# MOTOR_DRIVER.net
KiCad netlist of a schematic drawn in Altium Designer
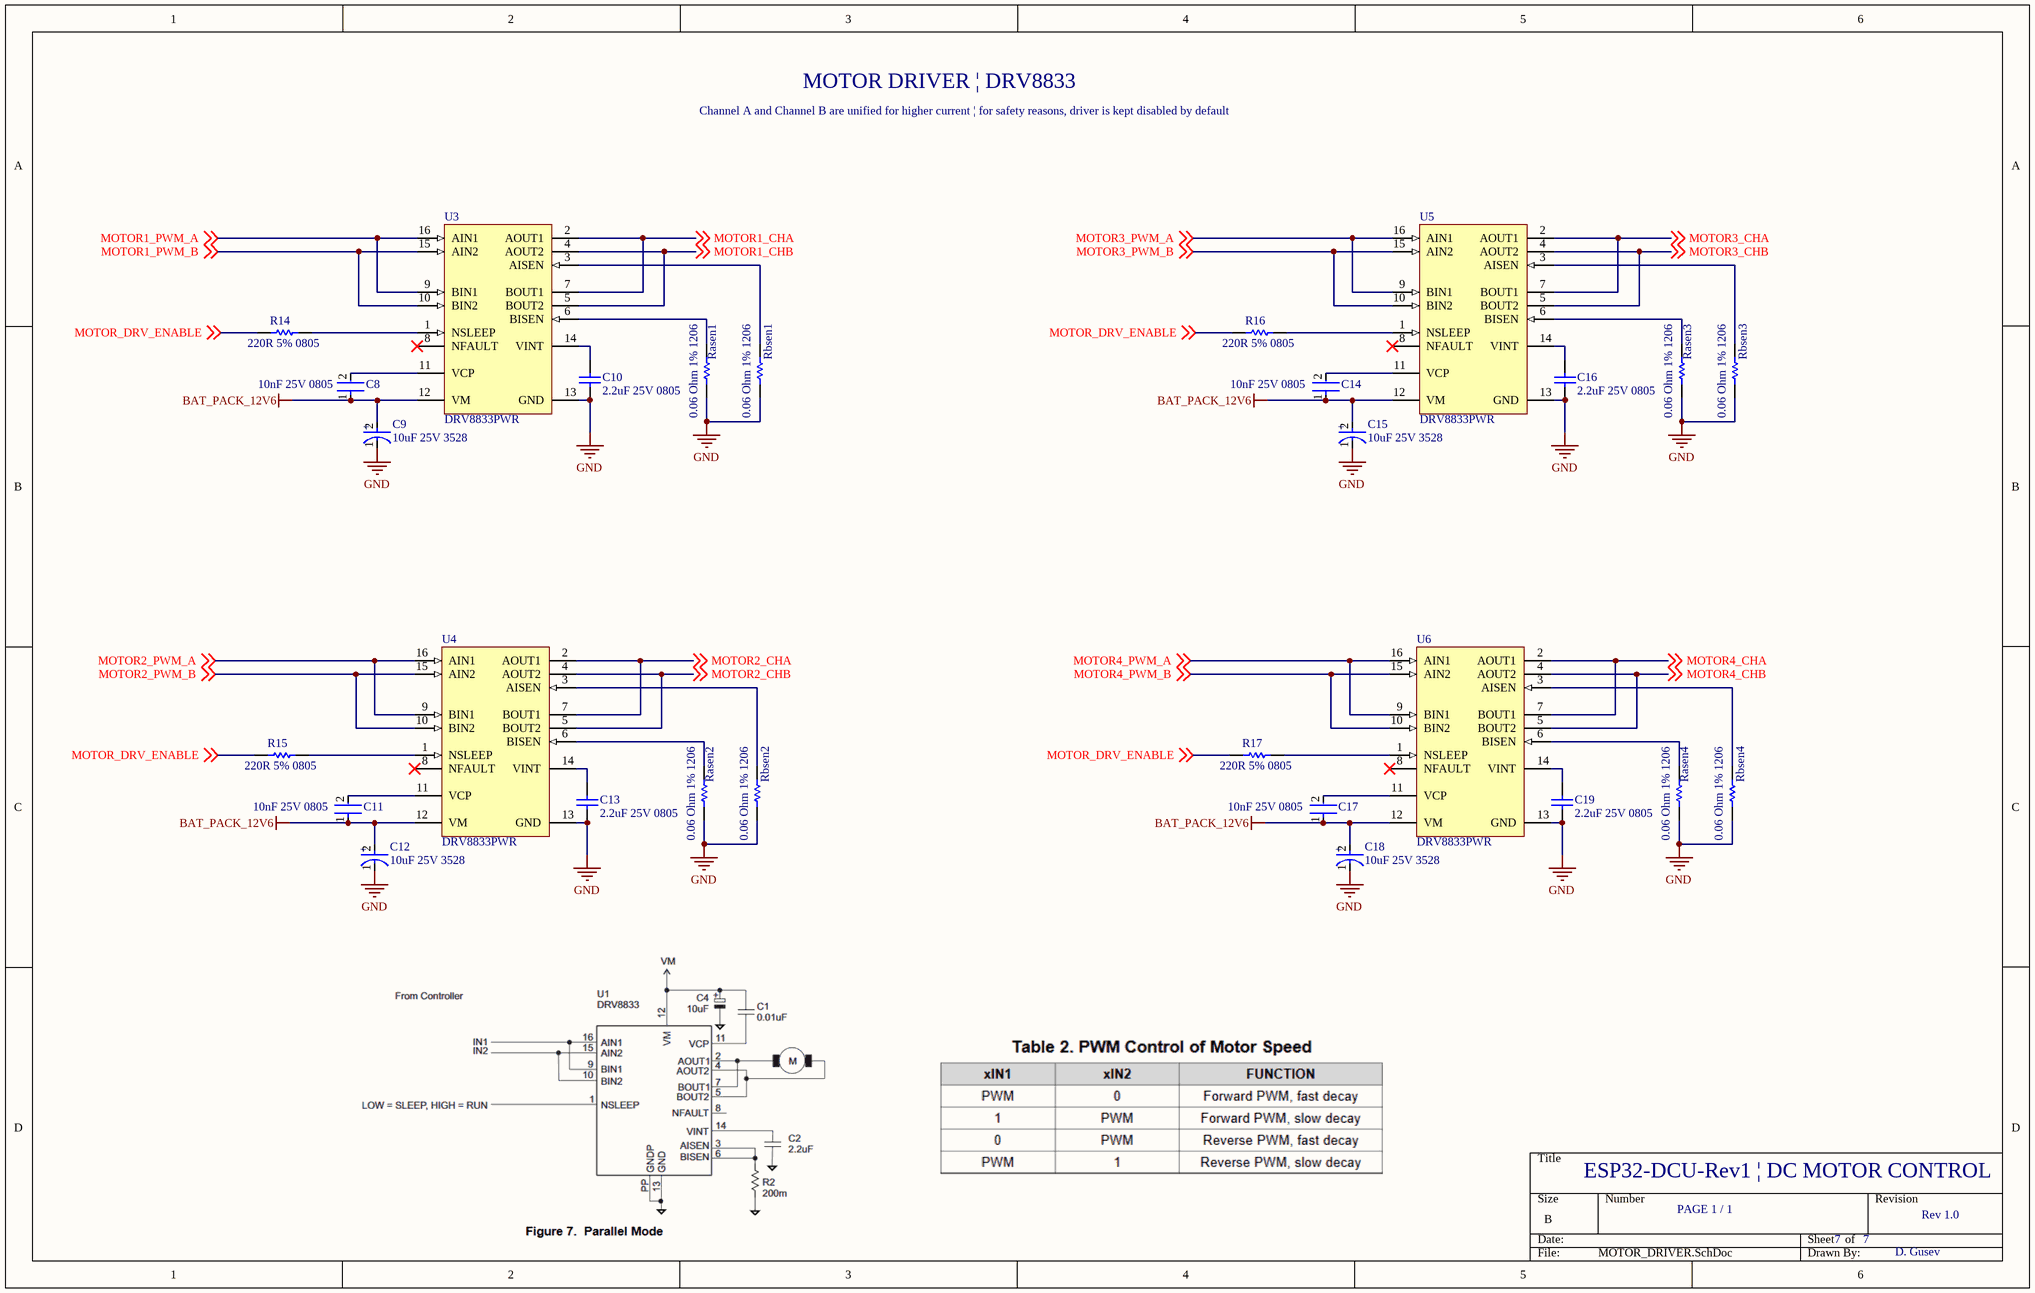
[diagram p0: MOTOR_DRIVER.SchDoc]

(export (version "E")
  (design (tool "Eeschema 10.0.6"))
  (components
    (comp (ref "C8")
      (value "10nF 25V 0805")
      (footprint "FP-C0805C-DN-MFG")
      (description "CAP CER 10000PF 25V 5% NP0 0805")
      (fields
        (field (name "OCTOPART") "https://octopart.com/c0805c103j3gactu-kemet-12563663")
        (field (name "TOLERANCE") "0.05")
      )
      (libsource (lib "Altium Content Vault") (part "b4654b650e69147ec39a6b967a45e02"))
    )
    (comp (ref "C9")
      (value "10uF 25V 3528")
      (footprint "FP-T491B106K025AT-MFG")
      (description "CAP TANT 10UF 10% 25V 1411")
      (fields (field (name "VOLTAGE") "25V") (field (name "TOLERANCE") "10%"))
      (libsource (lib "Altium Content Vault") (part "a00bbbee19879c290e62620ae7e47b1"))
    )
    (comp (ref "C10")
      (value "2.2uF 25V 0805")
      (footprint "CAPC2013X135X45ML10T25")
      (fields (field (name "PART NUMBER") "GRM21BF51E225ZA01L") (field (name "MANUFACTURER") "Murata"))
      (libsource (lib "Altium Content Vault") (part "CAP"))
    )
    (comp (ref "C11")
      (value "10nF 25V 0805")
      (footprint "FP-C0805C-DN-MFG")
      (description "CAP CER 10000PF 25V 5% NP0 0805")
      (fields
        (field (name "OCTOPART") "https://octopart.com/c0805c103j3gactu-kemet-12563663")
        (field (name "TOLERANCE") "0.05")
      )
      (libsource (lib "Altium Content Vault") (part "b4654b650e69147ec39a6b967a45e02"))
    )
    (comp (ref "C12")
      (value "10uF 25V 3528")
      (footprint "FP-T491B106K025AT-MFG")
      (description "CAP TANT 10UF 10% 25V 1411")
      (fields (field (name "VOLTAGE") "25V") (field (name "TOLERANCE") "10%"))
      (libsource (lib "Altium Content Vault") (part "a00bbbee19879c290e62620ae7e47b1"))
    )
    (comp (ref "C13")
      (value "2.2uF 25V 0805")
      (footprint "CAPC2013X135X45ML10T25")
      (fields (field (name "PART NUMBER") "GRM21BF51E225ZA01L") (field (name "MANUFACTURER") "Murata"))
      (libsource (lib "Altium Content Vault") (part "CAP"))
    )
    (comp (ref "C14")
      (value "10nF 25V 0805")
      (footprint "FP-C0805C-DN-MFG")
      (description "CAP CER 10000PF 25V 5% NP0 0805")
      (fields
        (field (name "OCTOPART") "https://octopart.com/c0805c103j3gactu-kemet-12563663")
        (field (name "TOLERANCE") "0.05")
      )
      (libsource (lib "Altium Content Vault") (part "b4654b650e69147ec39a6b967a45e02"))
    )
    (comp (ref "C15")
      (value "10uF 25V 3528")
      (footprint "FP-T491B106K025AT-MFG")
      (description "CAP TANT 10UF 10% 25V 1411")
      (fields (field (name "VOLTAGE") "25V") (field (name "TOLERANCE") "10%"))
      (libsource (lib "Altium Content Vault") (part "a00bbbee19879c290e62620ae7e47b1"))
    )
    (comp (ref "C16")
      (value "2.2uF 25V 0805")
      (footprint "CAPC2013X135X45ML10T25")
      (fields (field (name "PART NUMBER") "GRM21BF51E225ZA01L") (field (name "MANUFACTURER") "Murata"))
      (libsource (lib "Altium Content Vault") (part "CAP"))
    )
    (comp (ref "C17")
      (value "10nF 25V 0805")
      (footprint "FP-C0805C-DN-MFG")
      (description "CAP CER 10000PF 25V 5% NP0 0805")
      (fields
        (field (name "OCTOPART") "https://octopart.com/c0805c103j3gactu-kemet-12563663")
        (field (name "TOLERANCE") "0.05")
      )
      (libsource (lib "Altium Content Vault") (part "b4654b650e69147ec39a6b967a45e02"))
    )
    (comp (ref "C18")
      (value "10uF 25V 3528")
      (footprint "FP-T491B106K025AT-MFG")
      (description "CAP TANT 10UF 10% 25V 1411")
      (fields (field (name "VOLTAGE") "25V") (field (name "TOLERANCE") "10%"))
      (libsource (lib "Altium Content Vault") (part "a00bbbee19879c290e62620ae7e47b1"))
    )
    (comp (ref "C19")
      (value "2.2uF 25V 0805")
      (footprint "CAPC2013X135X45ML10T25")
      (fields (field (name "PART NUMBER") "GRM21BF51E225ZA01L") (field (name "MANUFACTURER") "Murata"))
      (libsource (lib "Altium Content Vault") (part "CAP"))
    )
    (comp (ref "R14")
      (value "220R 5% 0805")
      (footprint "RESC2013X60X40NL20T25")
      (fields (field (name "MANUFACTURER") "Panasonic") (field (name "PART NUMBER") "ERA6AEB221V"))
      (libsource (lib "Altium Content Vault") (part "RES"))
    )
    (comp (ref "R15")
      (value "220R 5% 0805")
      (footprint "RESC2013X60X40NL20T25")
      (fields (field (name "MANUFACTURER") "Panasonic") (field (name "PART NUMBER") "ERA6AEB221V"))
      (libsource (lib "Altium Content Vault") (part "RES"))
    )
    (comp (ref "R16")
      (value "220R 5% 0805")
      (footprint "RESC2013X60X40NL20T25")
      (fields (field (name "MANUFACTURER") "Panasonic") (field (name "PART NUMBER") "ERA6AEB221V"))
      (libsource (lib "Altium Content Vault") (part "RES"))
    )
    (comp (ref "R17")
      (value "220R 5% 0805")
      (footprint "RESC2013X60X40NL20T25")
      (fields (field (name "MANUFACTURER") "Panasonic") (field (name "PART NUMBER") "ERA6AEB221V"))
      (libsource (lib "Altium Content Vault") (part "RES"))
    )
    (comp (ref "Rasen1")
      (value "0.06 Ohm 1% 1206")
      (footprint "RESC3216X89X51NL25T25")
      (fields (field (name "MANUFACTURER") "Vishay Dale") (field (name "PART NUMBER") "WSL1206R0600FEA"))
      (libsource (lib "Altium Content Vault") (part "RES"))
    )
    (comp (ref "Rasen2")
      (value "0.06 Ohm 1% 1206")
      (footprint "RESC3216X89X51NL25T25")
      (fields (field (name "MANUFACTURER") "Vishay Dale") (field (name "PART NUMBER") "WSL1206R0600FEA"))
      (libsource (lib "Altium Content Vault") (part "RES"))
    )
    (comp (ref "Rasen3")
      (value "0.06 Ohm 1% 1206")
      (footprint "RESC3216X89X51NL25T25")
      (fields (field (name "MANUFACTURER") "Vishay Dale") (field (name "PART NUMBER") "WSL1206R0600FEA"))
      (libsource (lib "Altium Content Vault") (part "RES"))
    )
    (comp (ref "Rasen4")
      (value "0.06 Ohm 1% 1206")
      (footprint "RESC3216X89X51NL25T25")
      (fields (field (name "MANUFACTURER") "Vishay Dale") (field (name "PART NUMBER") "WSL1206R0600FEA"))
      (libsource (lib "Altium Content Vault") (part "RES"))
    )
    (comp (ref "Rbsen1")
      (value "0.06 Ohm 1% 1206")
      (footprint "RESC3216X89X51NL25T25")
      (fields (field (name "MANUFACTURER") "Vishay Dale") (field (name "PART NUMBER") "WSL1206R0600FEA"))
      (libsource (lib "Altium Content Vault") (part "RES"))
    )
    (comp (ref "Rbsen2")
      (value "0.06 Ohm 1% 1206")
      (footprint "RESC3216X89X51NL25T25")
      (fields (field (name "MANUFACTURER") "Vishay Dale") (field (name "PART NUMBER") "WSL1206R0600FEA"))
      (libsource (lib "Altium Content Vault") (part "RES"))
    )
    (comp (ref "Rbsen3")
      (value "0.06 Ohm 1% 1206")
      (footprint "RESC3216X89X51NL25T25")
      (fields (field (name "MANUFACTURER") "Vishay Dale") (field (name "PART NUMBER") "WSL1206R0600FEA"))
      (libsource (lib "Altium Content Vault") (part "RES"))
    )
    (comp (ref "Rbsen4")
      (value "0.06 Ohm 1% 1206")
      (footprint "RESC3216X89X51NL25T25")
      (fields (field (name "MANUFACTURER") "Vishay Dale") (field (name "PART NUMBER") "WSL1206R0600FEA"))
      (libsource (lib "Altium Content Vault") (part "RES"))
    )
    (comp (ref "U3")
      (value "DRV8833PWR")
      (footprint "PW0016A_L")
      (fields (field (name "MANUFACTURER") "Texas Instruments"))
      (libsource (lib "Altium Content Vault") (part "TI-DRV8833PW-16"))
    )
    (comp (ref "U4")
      (value "DRV8833PWR")
      (footprint "PW0016A_L")
      (fields (field (name "MANUFACTURER") "Texas Instruments"))
      (libsource (lib "Altium Content Vault") (part "TI-DRV8833PW-16"))
    )
    (comp (ref "U5")
      (value "DRV8833PWR")
      (footprint "PW0016A_L")
      (fields (field (name "MANUFACTURER") "Texas Instruments"))
      (libsource (lib "Altium Content Vault") (part "TI-DRV8833PW-16"))
    )
    (comp (ref "U6")
      (value "DRV8833PWR")
      (footprint "PW0016A_L")
      (fields (field (name "MANUFACTURER") "Texas Instruments"))
      (libsource (lib "Altium Content Vault") (part "TI-DRV8833PW-16"))
    )
  )
  (nets
    (net (code "1") (name "BAT_PACK_12V6") (class "Default")
      (node (ref "C11") (pin "1") (pinfunction "1_1") (pintype "passive"))
      (node (ref "C12") (pin "2") (pinfunction "A_2") (pintype "passive"))
      (node (ref "C14") (pin "1") (pinfunction "1_1") (pintype "passive"))
      (node (ref "C15") (pin "2") (pinfunction "A_2") (pintype "passive"))
      (node (ref "C17") (pin "1") (pinfunction "1_1") (pintype "passive"))
      (node (ref "C18") (pin "2") (pinfunction "A_2") (pintype "passive"))
      (node (ref "C8") (pin "1") (pinfunction "1_1") (pintype "passive"))
      (node (ref "C9") (pin "2") (pinfunction "A_2") (pintype "passive"))
      (node (ref "U3") (pin "12") (pinfunction "VM_12") (pintype "power_in"))
      (node (ref "U4") (pin "12") (pinfunction "VM_12") (pintype "power_in"))
      (node (ref "U5") (pin "12") (pinfunction "VM_12") (pintype "power_in"))
      (node (ref "U6") (pin "12") (pinfunction "VM_12") (pintype "power_in"))
    )
    (net (code "2") (name "GND") (class "Default")
      (node (ref "C10") (pin "1") (pinfunction "1_1") (pintype "passive"))
      (node (ref "C12") (pin "1") (pinfunction "C_1") (pintype "passive"))
      (node (ref "C13") (pin "1") (pinfunction "1_1") (pintype "passive"))
      (node (ref "C15") (pin "1") (pinfunction "C_1") (pintype "passive"))
      (node (ref "C16") (pin "1") (pinfunction "1_1") (pintype "passive"))
      (node (ref "C18") (pin "1") (pinfunction "C_1") (pintype "passive"))
      (node (ref "C19") (pin "1") (pinfunction "1_1") (pintype "passive"))
      (node (ref "C9") (pin "1") (pinfunction "C_1") (pintype "passive"))
      (node (ref "Rasen1") (pin "1") (pinfunction "1_1") (pintype "passive"))
      (node (ref "Rasen2") (pin "1") (pinfunction "1_1") (pintype "passive"))
      (node (ref "Rasen3") (pin "1") (pinfunction "1_1") (pintype "passive"))
      (node (ref "Rasen4") (pin "1") (pinfunction "1_1") (pintype "passive"))
      (node (ref "Rbsen1") (pin "1") (pinfunction "1_1") (pintype "passive"))
      (node (ref "Rbsen2") (pin "1") (pinfunction "1_1") (pintype "passive"))
      (node (ref "Rbsen3") (pin "1") (pinfunction "1_1") (pintype "passive"))
      (node (ref "Rbsen4") (pin "1") (pinfunction "1_1") (pintype "passive"))
      (node (ref "U3") (pin "13") (pinfunction "GND_13") (pintype "power_in"))
      (node (ref "U4") (pin "13") (pinfunction "GND_13") (pintype "power_in"))
      (node (ref "U5") (pin "13") (pinfunction "GND_13") (pintype "power_in"))
      (node (ref "U6") (pin "13") (pinfunction "GND_13") (pintype "power_in"))
    )
    (net (code "3") (name "MOTOR1_CHA") (class "Default")
      (node (ref "U3") (pin "2") (pinfunction "AOUT1_2") (pintype "tri_state"))
      (node (ref "U3") (pin "7") (pinfunction "BOUT1_7") (pintype "tri_state"))
    )
    (net (code "4") (name "MOTOR1_CHB") (class "Default")
      (node (ref "U3") (pin "4") (pinfunction "AOUT2_4") (pintype "tri_state"))
      (node (ref "U3") (pin "5") (pinfunction "BOUT2_5") (pintype "tri_state"))
    )
    (net (code "5") (name "MOTOR1_PWM_A") (class "Default")
      (node (ref "U3") (pin "16") (pinfunction "AIN1_16") (pintype "input"))
      (node (ref "U3") (pin "9") (pinfunction "BIN1_9") (pintype "input"))
    )
    (net (code "6") (name "MOTOR1_PWM_B") (class "Default")
      (node (ref "U3") (pin "10") (pinfunction "BIN2_10") (pintype "input"))
      (node (ref "U3") (pin "15") (pinfunction "AIN2_15") (pintype "input"))
    )
    (net (code "7") (name "MOTOR2_CHA") (class "Default")
      (node (ref "U4") (pin "2") (pinfunction "AOUT1_2") (pintype "tri_state"))
      (node (ref "U4") (pin "7") (pinfunction "BOUT1_7") (pintype "tri_state"))
    )
    (net (code "8") (name "MOTOR2_CHB") (class "Default")
      (node (ref "U4") (pin "4") (pinfunction "AOUT2_4") (pintype "tri_state"))
      (node (ref "U4") (pin "5") (pinfunction "BOUT2_5") (pintype "tri_state"))
    )
    (net (code "9") (name "MOTOR2_PWM_A") (class "Default")
      (node (ref "U4") (pin "16") (pinfunction "AIN1_16") (pintype "input"))
      (node (ref "U4") (pin "9") (pinfunction "BIN1_9") (pintype "input"))
    )
    (net (code "10") (name "MOTOR2_PWM_B") (class "Default")
      (node (ref "U4") (pin "10") (pinfunction "BIN2_10") (pintype "input"))
      (node (ref "U4") (pin "15") (pinfunction "AIN2_15") (pintype "input"))
    )
    (net (code "11") (name "MOTOR3_CHA") (class "Default")
      (node (ref "U5") (pin "2") (pinfunction "AOUT1_2") (pintype "tri_state"))
      (node (ref "U5") (pin "7") (pinfunction "BOUT1_7") (pintype "tri_state"))
    )
    (net (code "12") (name "MOTOR3_CHB") (class "Default")
      (node (ref "U5") (pin "4") (pinfunction "AOUT2_4") (pintype "tri_state"))
      (node (ref "U5") (pin "5") (pinfunction "BOUT2_5") (pintype "tri_state"))
    )
    (net (code "13") (name "MOTOR3_PWM_A") (class "Default")
      (node (ref "U5") (pin "16") (pinfunction "AIN1_16") (pintype "input"))
      (node (ref "U5") (pin "9") (pinfunction "BIN1_9") (pintype "input"))
    )
    (net (code "14") (name "MOTOR3_PWM_B") (class "Default")
      (node (ref "U5") (pin "10") (pinfunction "BIN2_10") (pintype "input"))
      (node (ref "U5") (pin "15") (pinfunction "AIN2_15") (pintype "input"))
    )
    (net (code "15") (name "MOTOR4_CHA") (class "Default")
      (node (ref "U6") (pin "2") (pinfunction "AOUT1_2") (pintype "tri_state"))
      (node (ref "U6") (pin "7") (pinfunction "BOUT1_7") (pintype "tri_state"))
    )
    (net (code "16") (name "MOTOR4_CHB") (class "Default")
      (node (ref "U6") (pin "4") (pinfunction "AOUT2_4") (pintype "tri_state"))
      (node (ref "U6") (pin "5") (pinfunction "BOUT2_5") (pintype "tri_state"))
    )
    (net (code "17") (name "MOTOR4_PWM_A") (class "Default")
      (node (ref "U6") (pin "16") (pinfunction "AIN1_16") (pintype "input"))
      (node (ref "U6") (pin "9") (pinfunction "BIN1_9") (pintype "input"))
    )
    (net (code "18") (name "MOTOR4_PWM_B") (class "Default")
      (node (ref "U6") (pin "10") (pinfunction "BIN2_10") (pintype "input"))
      (node (ref "U6") (pin "15") (pinfunction "AIN2_15") (pintype "input"))
    )
    (net (code "19") (name "MOTOR_DRV_ENABLE") (class "Default")
      (node (ref "R14") (pin "1") (pinfunction "1_1") (pintype "passive"))
      (node (ref "R15") (pin "1") (pinfunction "1_1") (pintype "passive"))
      (node (ref "R16") (pin "1") (pinfunction "1_1") (pintype "passive"))
      (node (ref "R17") (pin "1") (pinfunction "1_1") (pintype "passive"))
    )
    (net (code "20") (name "Net-(U3-AISEN)") (class "Default")
      (node (ref "Rbsen1") (pin "2") (pinfunction "2_2") (pintype "passive"))
      (node (ref "U3") (pin "3") (pinfunction "AISEN_3") (pintype "input"))
    )
    (net (code "21") (name "Net-(U3-BISEN)") (class "Default")
      (node (ref "Rasen1") (pin "2") (pinfunction "2_2") (pintype "passive"))
      (node (ref "U3") (pin "6") (pinfunction "BISEN_6") (pintype "input"))
    )
    (net (code "22") (name "Net-(U3-NSLEEP)") (class "Default")
      (node (ref "R14") (pin "2") (pinfunction "2_2") (pintype "passive"))
      (node (ref "U3") (pin "1") (pinfunction "NSLEEP_1") (pintype "input"))
    )
    (net (code "23") (name "Net-(U3-VCP)") (class "Default")
      (node (ref "C8") (pin "2") (pinfunction "2_2") (pintype "passive"))
      (node (ref "U3") (pin "11") (pinfunction "VCP_11") (pintype "passive"))
    )
    (net (code "24") (name "Net-(U3-VINT)") (class "Default")
      (node (ref "C10") (pin "2") (pinfunction "2_2") (pintype "passive"))
      (node (ref "U3") (pin "14") (pinfunction "VINT_14") (pintype "passive"))
    )
    (net (code "25") (name "Net-(U4-AISEN)") (class "Default")
      (node (ref "Rbsen2") (pin "2") (pinfunction "2_2") (pintype "passive"))
      (node (ref "U4") (pin "3") (pinfunction "AISEN_3") (pintype "input"))
    )
    (net (code "26") (name "Net-(U4-BISEN)") (class "Default")
      (node (ref "Rasen2") (pin "2") (pinfunction "2_2") (pintype "passive"))
      (node (ref "U4") (pin "6") (pinfunction "BISEN_6") (pintype "input"))
    )
    (net (code "27") (name "Net-(U4-NSLEEP)") (class "Default")
      (node (ref "R15") (pin "2") (pinfunction "2_2") (pintype "passive"))
      (node (ref "U4") (pin "1") (pinfunction "NSLEEP_1") (pintype "input"))
    )
    (net (code "28") (name "Net-(U4-VCP)") (class "Default")
      (node (ref "C11") (pin "2") (pinfunction "2_2") (pintype "passive"))
      (node (ref "U4") (pin "11") (pinfunction "VCP_11") (pintype "passive"))
    )
    (net (code "29") (name "Net-(U4-VINT)") (class "Default")
      (node (ref "C13") (pin "2") (pinfunction "2_2") (pintype "passive"))
      (node (ref "U4") (pin "14") (pinfunction "VINT_14") (pintype "passive"))
    )
    (net (code "30") (name "Net-(U5-AISEN)") (class "Default")
      (node (ref "Rbsen3") (pin "2") (pinfunction "2_2") (pintype "passive"))
      (node (ref "U5") (pin "3") (pinfunction "AISEN_3") (pintype "input"))
    )
    (net (code "31") (name "Net-(U5-BISEN)") (class "Default")
      (node (ref "Rasen3") (pin "2") (pinfunction "2_2") (pintype "passive"))
      (node (ref "U5") (pin "6") (pinfunction "BISEN_6") (pintype "input"))
    )
    (net (code "32") (name "Net-(U5-NSLEEP)") (class "Default")
      (node (ref "R16") (pin "2") (pinfunction "2_2") (pintype "passive"))
      (node (ref "U5") (pin "1") (pinfunction "NSLEEP_1") (pintype "input"))
    )
    (net (code "33") (name "Net-(U5-VCP)") (class "Default")
      (node (ref "C14") (pin "2") (pinfunction "2_2") (pintype "passive"))
      (node (ref "U5") (pin "11") (pinfunction "VCP_11") (pintype "passive"))
    )
    (net (code "34") (name "Net-(U5-VINT)") (class "Default")
      (node (ref "C16") (pin "2") (pinfunction "2_2") (pintype "passive"))
      (node (ref "U5") (pin "14") (pinfunction "VINT_14") (pintype "passive"))
    )
    (net (code "35") (name "Net-(U6-AISEN)") (class "Default")
      (node (ref "Rbsen4") (pin "2") (pinfunction "2_2") (pintype "passive"))
      (node (ref "U6") (pin "3") (pinfunction "AISEN_3") (pintype "input"))
    )
    (net (code "36") (name "Net-(U6-BISEN)") (class "Default")
      (node (ref "Rasen4") (pin "2") (pinfunction "2_2") (pintype "passive"))
      (node (ref "U6") (pin "6") (pinfunction "BISEN_6") (pintype "input"))
    )
    (net (code "37") (name "Net-(U6-NSLEEP)") (class "Default")
      (node (ref "R17") (pin "2") (pinfunction "2_2") (pintype "passive"))
      (node (ref "U6") (pin "1") (pinfunction "NSLEEP_1") (pintype "input"))
    )
    (net (code "38") (name "Net-(U6-VCP)") (class "Default")
      (node (ref "C17") (pin "2") (pinfunction "2_2") (pintype "passive"))
      (node (ref "U6") (pin "11") (pinfunction "VCP_11") (pintype "passive"))
    )
    (net (code "39") (name "Net-(U6-VINT)") (class "Default")
      (node (ref "C19") (pin "2") (pinfunction "2_2") (pintype "passive"))
      (node (ref "U6") (pin "14") (pinfunction "VINT_14") (pintype "passive"))
    )
    (net (code "40") (name "unconnected-(U3-NFAULT-Pad8)") (class "Default")
      (node (ref "U3") (pin "8") (pinfunction "NFAULT_8") (pintype "open_collector+no_connect"))
    )
    (net (code "41") (name "unconnected-(U4-NFAULT-Pad8)") (class "Default")
      (node (ref "U4") (pin "8") (pinfunction "NFAULT_8") (pintype "open_collector+no_connect"))
    )
    (net (code "42") (name "unconnected-(U5-NFAULT-Pad8)") (class "Default")
      (node (ref "U5") (pin "8") (pinfunction "NFAULT_8") (pintype "open_collector+no_connect"))
    )
    (net (code "43") (name "unconnected-(U6-NFAULT-Pad8)") (class "Default")
      (node (ref "U6") (pin "8") (pinfunction "NFAULT_8") (pintype "open_collector+no_connect"))
    )
  )
)
